# Nixie_1.net
KiCad netlist of a schematic drawn in Altium Designer
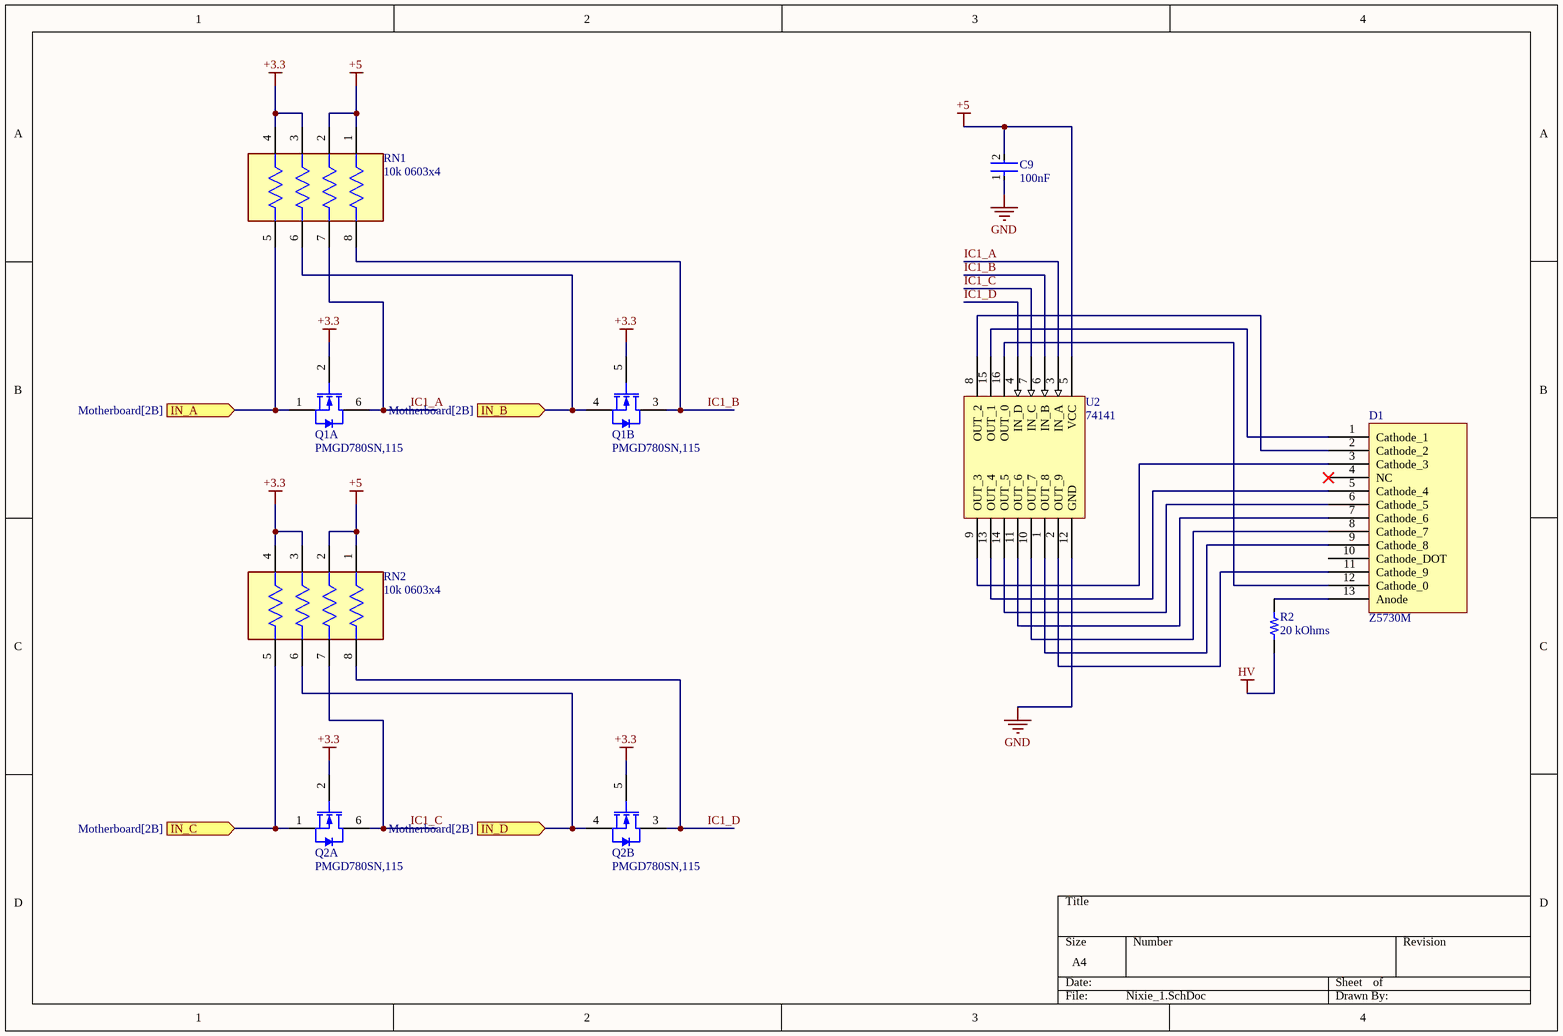
[diagram p0: Nixie_1.SchDoc]

(export (version "E")
  (design (tool "Eeschema 10.0.6"))
  (components
    (comp (ref "C9")
      (value "100nF")
      (footprint "FP-C1005-050-0_15-MFG")
      (description "CAP CER 100nF 10V X5R 0402")
      (fields (field (name "TOLERANCE") "20%") (field (name "VOLTAGE") "10V"))
      (libsource (lib "Altium Content Vault") (part "11868f565c42a9108669ba33697ecf6"))
    )
    (comp (ref "D1") (value "Z5730M") (footprint "Z5730M") (libsource (lib "Z5730M") (part "Z5730M")))
    (comp (ref "Q1")
      (value "PMGD780SN,115")
      (footprint "NXP-SOT363_N")
      (description "Dual N-Channel uTrenchMOS Standard Level FET, 60 V, 0.49 A, 6-Pin SOT363, Tape and Reel")
      (fields (field (name "MANUFACTURER") "NXP Semiconductors"))
      (libsource (lib "Altium Content Vault") (part "NXP-NNMOS-SGDSGD-6_B"))
    )
    (comp (ref "Q2")
      (value "PMGD780SN,115")
      (footprint "NXP-SOT363_N")
      (description "Dual N-Channel uTrenchMOS Standard Level FET, 60 V, 0.49 A, 6-Pin SOT363, Tape and Reel")
      (fields (field (name "MANUFACTURER") "NXP Semiconductors"))
      (libsource (lib "Altium Content Vault") (part "NXP-NNMOS-SGDSGD-6_B"))
    )
    (comp (ref "R2")
      (value "20 kOhms")
      (footprint "RES 1210_3225")
      (description "RES SMD 20K OHM 1% 3/4W 1210")
      (fields (field (name "PART NUMBER") "CRCW121020K0FKEAHP") (field (name "MANUFACTURER") "Vishay Dale"))
      (libsource (lib "Celestial Altium Library - altium_library") (part "Resistor"))
    )
    (comp (ref "RN1")
      (value "10k 0603x4")
      (footprint "FP-EXB38V-MFG")
      (description "RES ARRAY 4 RES 10K OHM 1206\r\nRC-ML08W103JT")
      (fields (field (name "TOLERANCE") "5%"))
      (libsource (lib "Altium Content Vault") (part "2ca08171d0bbdee8be62227dae509d7"))
    )
    (comp (ref "RN2")
      (value "10k 0603x4")
      (footprint "FP-EXB38V-MFG")
      (description "RES ARRAY 4 RES 10K OHM 1206\r\nRC-ML08W103JT")
      (fields (field (name "TOLERANCE") "5%"))
      (libsource (lib "Altium Content Vault") (part "2ca08171d0bbdee8be62227dae509d7"))
    )
    (comp (ref "U2") (value "74141") (footprint "DIP-16") (libsource (lib "Z5730M") (part "74141")))
  )
  (nets
    (net (code "1") (name "+3.3") (class "Default")
      (node (ref "Q1") (pin "2") (pinfunction "G1_2") (pintype "passive"))
      (node (ref "Q1") (pin "5") (pinfunction "G2_5") (pintype "passive"))
      (node (ref "Q2") (pin "2") (pinfunction "G1_2") (pintype "passive"))
      (node (ref "Q2") (pin "5") (pinfunction "G2_5") (pintype "passive"))
      (node (ref "RN1") (pin "3") (pinfunction "3_3") (pintype "passive"))
      (node (ref "RN1") (pin "4") (pinfunction "4_4") (pintype "passive"))
      (node (ref "RN2") (pin "3") (pinfunction "3_3") (pintype "passive"))
      (node (ref "RN2") (pin "4") (pinfunction "4_4") (pintype "passive"))
    )
    (net (code "2") (name "+5") (class "Default")
      (node (ref "C9") (pin "2") (pinfunction "2_2") (pintype "passive"))
      (node (ref "RN1") (pin "1") (pinfunction "1_1") (pintype "passive"))
      (node (ref "RN1") (pin "2") (pinfunction "2_2") (pintype "passive"))
      (node (ref "RN2") (pin "1") (pinfunction "1_1") (pintype "passive"))
      (node (ref "RN2") (pin "2") (pinfunction "2_2") (pintype "passive"))
      (node (ref "U2") (pin "5") (pinfunction "VCC_5") (pintype "power_in"))
    )
    (net (code "3") (name "/IC1_A") (class "Default")
      (node (ref "Q1") (pin "6") (pinfunction "D1_6") (pintype "passive"))
      (node (ref "RN1") (pin "7") (pinfunction "7_7") (pintype "passive"))
      (node (ref "U2") (pin "3") (pinfunction "IN_A_3") (pintype "input"))
    )
    (net (code "4") (name "/IC1_B") (class "Default")
      (node (ref "Q1") (pin "3") (pinfunction "D2_3") (pintype "passive"))
      (node (ref "RN1") (pin "8") (pinfunction "8_8") (pintype "passive"))
      (node (ref "U2") (pin "6") (pinfunction "IN_B_6") (pintype "input"))
    )
    (net (code "5") (name "/IC1_C") (class "Default")
      (node (ref "Q2") (pin "6") (pinfunction "D1_6") (pintype "passive"))
      (node (ref "RN2") (pin "7") (pinfunction "7_7") (pintype "passive"))
      (node (ref "U2") (pin "7") (pinfunction "IN_C_7") (pintype "input"))
    )
    (net (code "6") (name "/IC1_D") (class "Default")
      (node (ref "Q2") (pin "3") (pinfunction "D2_3") (pintype "passive"))
      (node (ref "RN2") (pin "8") (pinfunction "8_8") (pintype "passive"))
      (node (ref "U2") (pin "4") (pinfunction "IN_D_4") (pintype "input"))
    )
    (net (code "7") (name "/IN_A") (class "Default")
      (node (ref "Q1") (pin "1") (pinfunction "S1_1") (pintype "passive"))
      (node (ref "RN1") (pin "5") (pinfunction "5_5") (pintype "passive"))
    )
    (net (code "8") (name "/IN_B") (class "Default")
      (node (ref "Q1") (pin "4") (pinfunction "S2_4") (pintype "passive"))
      (node (ref "RN1") (pin "6") (pinfunction "6_6") (pintype "passive"))
    )
    (net (code "9") (name "/IN_C") (class "Default")
      (node (ref "Q2") (pin "1") (pinfunction "S1_1") (pintype "passive"))
      (node (ref "RN2") (pin "5") (pinfunction "5_5") (pintype "passive"))
    )
    (net (code "10") (name "/IN_D") (class "Default")
      (node (ref "Q2") (pin "4") (pinfunction "S2_4") (pintype "passive"))
      (node (ref "RN2") (pin "6") (pinfunction "6_6") (pintype "passive"))
    )
    (net (code "11") (name "GND") (class "Default")
      (node (ref "C9") (pin "1") (pinfunction "1_1") (pintype "passive"))
      (node (ref "U2") (pin "12") (pinfunction "GND_12") (pintype "power_in"))
    )
    (net (code "12") (name "HV") (class "Default")
      (node (ref "R2") (pin "1") (pinfunction "1_1") (pintype "passive"))
    )
    (net (code "13") (name "Net-(D1-Anode)") (class "Default")
      (node (ref "D1") (pin "13") (pinfunction "Anode_13") (pintype "passive"))
      (node (ref "R2") (pin "2") (pinfunction "2_2") (pintype "passive"))
    )
    (net (code "14") (name "Net-(D1-Cathode_0)") (class "Default")
      (node (ref "D1") (pin "12") (pinfunction "Cathode_0_12") (pintype "passive"))
      (node (ref "U2") (pin "16") (pinfunction "OUT_0_16") (pintype "open_collector"))
    )
    (net (code "15") (name "Net-(D1-Cathode_1)") (class "Default")
      (node (ref "D1") (pin "1") (pinfunction "Cathode_1_1") (pintype "passive"))
      (node (ref "U2") (pin "15") (pinfunction "OUT_1_15") (pintype "open_collector"))
    )
    (net (code "16") (name "Net-(D1-Cathode_2)") (class "Default")
      (node (ref "D1") (pin "2") (pinfunction "Cathode_2_2") (pintype "passive"))
      (node (ref "U2") (pin "8") (pinfunction "OUT_2_8") (pintype "open_collector"))
    )
    (net (code "17") (name "Net-(D1-Cathode_3)") (class "Default")
      (node (ref "D1") (pin "3") (pinfunction "Cathode_3_3") (pintype "passive"))
      (node (ref "U2") (pin "9") (pinfunction "OUT_3_9") (pintype "open_collector"))
    )
    (net (code "18") (name "Net-(D1-Cathode_4)") (class "Default")
      (node (ref "D1") (pin "5") (pinfunction "Cathode_4_5") (pintype "passive"))
      (node (ref "U2") (pin "13") (pinfunction "OUT_4_13") (pintype "open_collector"))
    )
    (net (code "19") (name "Net-(D1-Cathode_5)") (class "Default")
      (node (ref "D1") (pin "6") (pinfunction "Cathode_5_6") (pintype "passive"))
      (node (ref "U2") (pin "14") (pinfunction "OUT_5_14") (pintype "open_collector"))
    )
    (net (code "20") (name "Net-(D1-Cathode_6)") (class "Default")
      (node (ref "D1") (pin "7") (pinfunction "Cathode_6_7") (pintype "passive"))
      (node (ref "U2") (pin "11") (pinfunction "OUT_6_11") (pintype "open_collector"))
    )
    (net (code "21") (name "Net-(D1-Cathode_7)") (class "Default")
      (node (ref "D1") (pin "8") (pinfunction "Cathode_7_8") (pintype "passive"))
      (node (ref "U2") (pin "10") (pinfunction "OUT_7_10") (pintype "open_collector"))
    )
    (net (code "22") (name "Net-(D1-Cathode_8)") (class "Default")
      (node (ref "D1") (pin "9") (pinfunction "Cathode_8_9") (pintype "passive"))
      (node (ref "U2") (pin "1") (pinfunction "OUT_8_1") (pintype "open_collector"))
    )
    (net (code "23") (name "Net-(D1-Cathode_9)") (class "Default")
      (node (ref "D1") (pin "11") (pinfunction "Cathode_9_11") (pintype "passive"))
      (node (ref "U2") (pin "2") (pinfunction "OUT_9_2") (pintype "open_collector"))
    )
    (net (code "24") (name "unconnected-(D1-Cathode_DOT-Pad10)") (class "Default")
      (node (ref "D1") (pin "10") (pinfunction "Cathode_DOT_10") (pintype "passive"))
    )
    (net (code "25") (name "unconnected-(D1-NC-Pad4)") (class "Default")
      (node (ref "D1") (pin "4") (pinfunction "NC_4") (pintype "passive+no_connect"))
    )
  )
)
